# pihat2.net
KiCad netlist of a schematic drawn in EAGLE
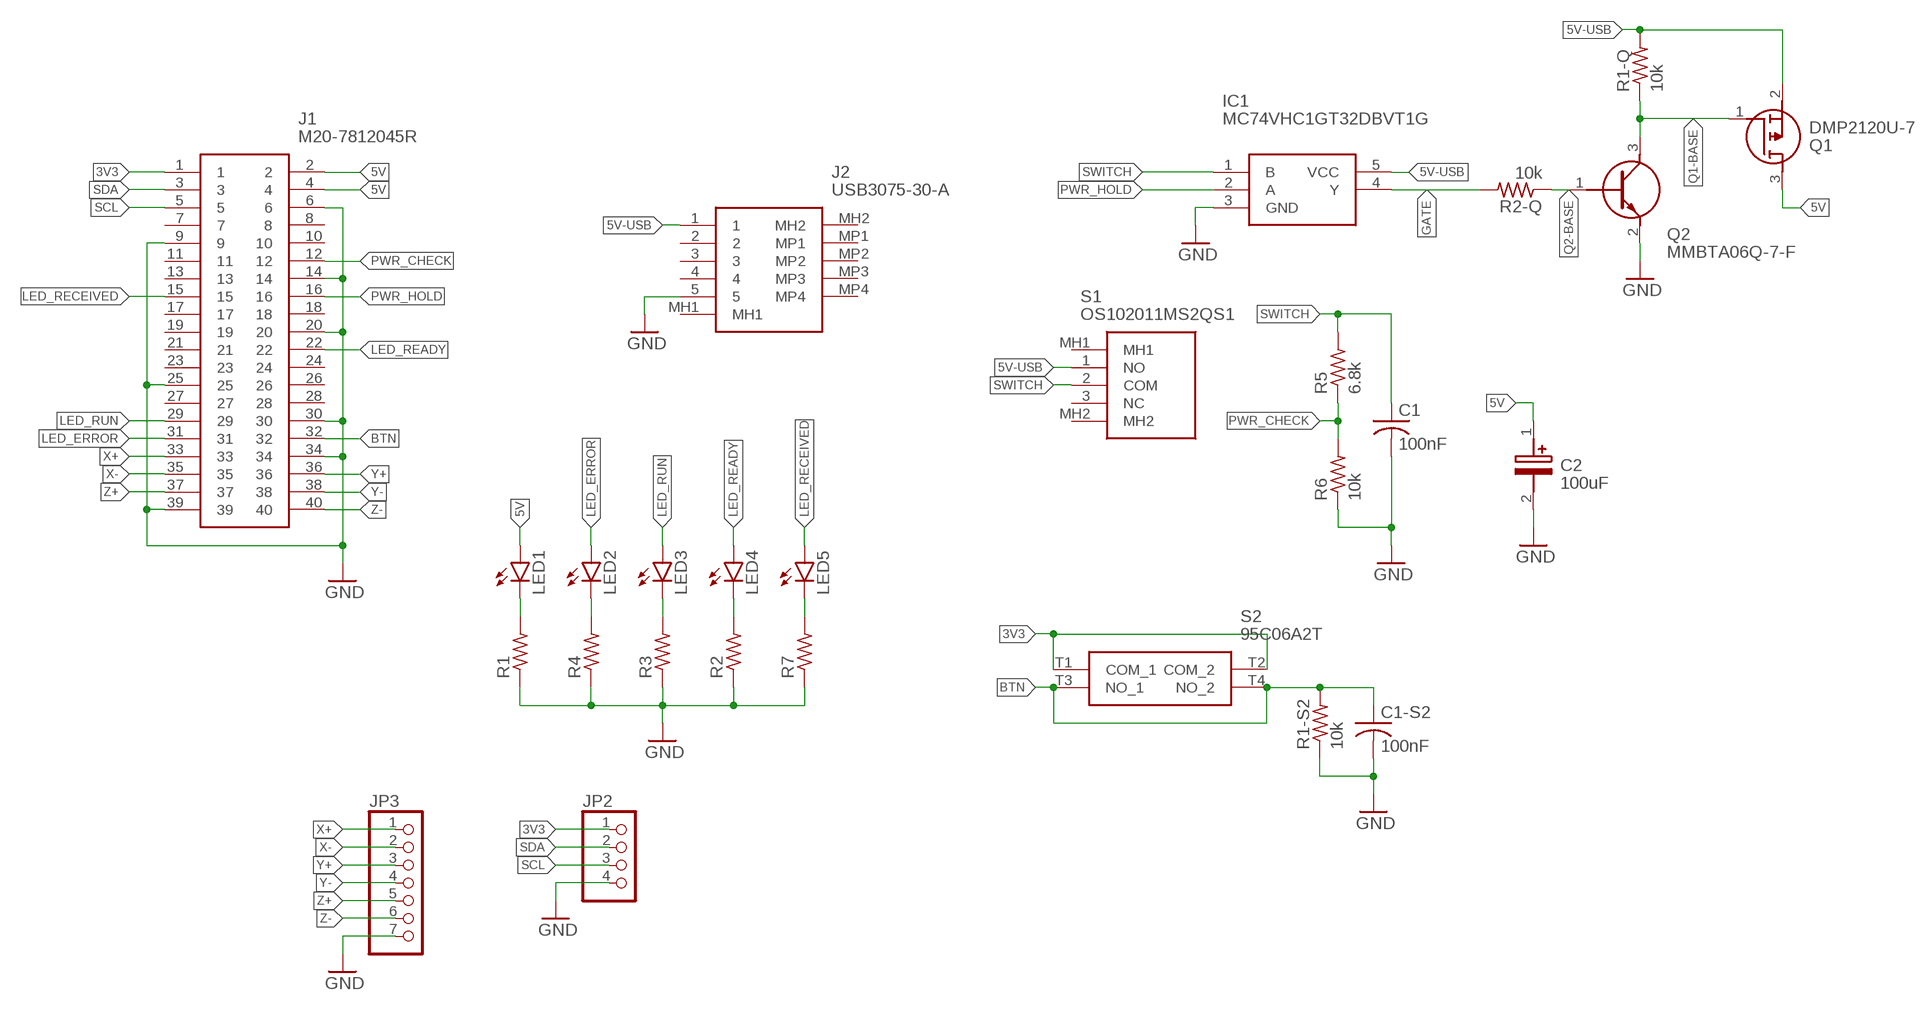
[diagram p0: schematic, sheet 1]

(export (version "E")
  (design (tool "Eeschema 10.0.6"))
  (components
    (comp (ref "C1")
      (value "100nF")
      (footprint "eagle-import:C0805")
      (libsource (lib "eagle-import") (part "C-USC0805"))
    )
    (comp (ref "C1-S2")
      (value "100nF")
      (footprint "eagle-import:C0805")
      (libsource (lib "eagle-import") (part "C-USC0805"))
    )
    (comp (ref "C2")
      (value "100uF")
      (footprint "eagle-import:CAPPRD250W45D630H500")
      (fields
        (field (name "MANUFACTURER_PART_NUMBER") "10ML100MEFC6.3X5")
        (field (name "MOUSER_PART_NUMBER") "232-10ML100MEFC6.3X5")
      )
      (libsource (lib "eagle-import") (part "10ML100MEFC6.3X5"))
    )
    (comp (ref "IC1")
      (value "MC74VHC1GT32DBVT1G")
      (footprint "eagle-import:MC74VHC1GT32DBVT1G")
      (fields (field (name "MOUSER_PART_NUMBER") "863-MC74VHC1GT32DBVG"))
      (libsource (lib "eagle-import") (part "MC74VHC1GT32DBVT1G"))
    )
    (comp (ref "J1")
      (value "M20-7812045R")
      (footprint "eagle-import:M207812045R")
      (fields (field (name "MOUSER_PART_NUMBER") "855-M20-7812045R"))
      (libsource (lib "eagle-import") (part "M20-7812045R"))
    )
    (comp (ref "J2")
      (value "USB3075-30-A")
      (footprint "eagle-import:USB307530A")
      (fields (field (name "MOUSER_PART_NUMBER") "640-USB3075-30-A"))
      (libsource (lib "eagle-import") (part "USB3075-30-A"))
    )
    (comp (ref "JP2")
      (value "PINHD-1X4")
      (footprint "eagle-import:1X04")
      (libsource (lib "eagle-import") (part "PINHD-1X4"))
    )
    (comp (ref "JP3")
      (value "PINHD-1X7")
      (footprint "eagle-import:1X07")
      (libsource (lib "eagle-import") (part "PINHD-1X7"))
    )
    (comp (ref "LED1")
      (value "LED5MM")
      (footprint "eagle-import:LED5MM")
      (libsource (lib "eagle-import") (part "LED5MM"))
    )
    (comp (ref "LED2")
      (value "LED5MM")
      (footprint "eagle-import:LED5MM")
      (libsource (lib "eagle-import") (part "LED5MM"))
    )
    (comp (ref "LED3")
      (value "LED5MM")
      (footprint "eagle-import:LED5MM")
      (libsource (lib "eagle-import") (part "LED5MM"))
    )
    (comp (ref "LED4")
      (value "LED5MM")
      (footprint "eagle-import:LED5MM")
      (libsource (lib "eagle-import") (part "LED5MM"))
    )
    (comp (ref "LED5")
      (value "LED5MM")
      (footprint "eagle-import:LED5MM")
      (libsource (lib "eagle-import") (part "LED5MM"))
    )
    (comp (ref "Q1")
      (value "DMP2120U-7")
      (footprint "eagle-import:SOT96P240X110-3N")
      (fields (field (name "MOUSER_PART_NUMBER") "621-DMP2120U-7"))
      (libsource (lib "eagle-import") (part "DMP2120U-7"))
    )
    (comp (ref "Q2")
      (value "MMBTA06Q-7-F")
      (footprint "eagle-import:SOT95P240X120-3N")
      (fields (field (name "MOUSER_PART_NUMBER") "621-MMBTA06Q-7-F"))
      (libsource (lib "eagle-import") (part "MMBTA06Q-7-F"))
    )
    (comp (ref "R1")
      (value "R-US_R0805")
      (footprint "eagle-import:R0805")
      (libsource (lib "eagle-import") (part "R-US_R0805"))
    )
    (comp (ref "R1-Q")
      (value "10k")
      (footprint "eagle-import:R0805")
      (libsource (lib "eagle-import") (part "R-US_R0805"))
    )
    (comp (ref "R1-S2")
      (value "10k")
      (footprint "eagle-import:R0805")
      (libsource (lib "eagle-import") (part "R-US_R0805"))
    )
    (comp (ref "R2")
      (value "R-US_R0805")
      (footprint "eagle-import:R0805")
      (libsource (lib "eagle-import") (part "R-US_R0805"))
    )
    (comp (ref "R2-Q")
      (value "10k")
      (footprint "eagle-import:R0805")
      (libsource (lib "eagle-import") (part "R-US_R0805"))
    )
    (comp (ref "R3")
      (value "R-US_R0805")
      (footprint "eagle-import:R0805")
      (libsource (lib "eagle-import") (part "R-US_R0805"))
    )
    (comp (ref "R4")
      (value "R-US_R0805")
      (footprint "eagle-import:R0805")
      (libsource (lib "eagle-import") (part "R-US_R0805"))
    )
    (comp (ref "R5")
      (value "6.8k")
      (footprint "eagle-import:R0805")
      (libsource (lib "eagle-import") (part "R-US_R0805"))
    )
    (comp (ref "R6")
      (value "10k")
      (footprint "eagle-import:R0805")
      (libsource (lib "eagle-import") (part "R-US_R0805"))
    )
    (comp (ref "R7")
      (value "R-US_R0805")
      (footprint "eagle-import:R0805")
      (libsource (lib "eagle-import") (part "R-US_R0805"))
    )
    (comp (ref "S1")
      (value "OS102011MS2QS1")
      (footprint "eagle-import:OS102011MS2QS1")
      (fields (field (name "MOUSER_PART_NUMBER") "611-OS102011MS2QS1"))
      (libsource (lib "eagle-import") (part "OS102011MS2QS1"))
    )
    (comp (ref "S2")
      (value "95C06A2T")
      (footprint "eagle-import:95C06A2T")
      (fields (field (name "MOUSER_PART_NUMBER") "706-95C06A2T"))
      (libsource (lib "eagle-import") (part "95C06A2T"))
    )
  )
  (nets
    (net (code "1") (name "3V3") (class "Default")
      (node (ref "J1") (pin "1") (pinfunction "1_1") (pintype "bidirectional"))
      (node (ref "JP2") (pin "1") (pinfunction "1_1") (pintype "passive"))
      (node (ref "S2") (pin "T1") (pinfunction "COM_1_T1") (pintype "bidirectional"))
      (node (ref "S2") (pin "T2") (pinfunction "COM_2_T2") (pintype "bidirectional"))
    )
    (net (code "2") (name "5V") (class "Default")
      (node (ref "C2") (pin "1") (pinfunction "+_1") (pintype "bidirectional"))
      (node (ref "J1") (pin "2") (pinfunction "2_2") (pintype "bidirectional"))
      (node (ref "J1") (pin "4") (pinfunction "4_4") (pintype "bidirectional"))
      (node (ref "LED1") (pin "A") (pinfunction "A_A") (pintype "passive"))
      (node (ref "Q1") (pin "3") (pinfunction "D_3") (pintype "bidirectional"))
    )
    (net (code "3") (name "5V-USB") (class "Default")
      (node (ref "IC1") (pin "5") (pinfunction "VCC_5") (pintype "bidirectional"))
      (node (ref "J2") (pin "1") (pinfunction "1_1") (pintype "bidirectional"))
      (node (ref "Q1") (pin "2") (pinfunction "S_2") (pintype "bidirectional"))
      (node (ref "R1-Q") (pin "2") (pinfunction "2_2") (pintype "passive"))
      (node (ref "S1") (pin "1") (pinfunction "NO_1") (pintype "bidirectional"))
    )
    (net (code "4") (name "BTN") (class "Default")
      (node (ref "C1-S2") (pin "1") (pinfunction "1_1") (pintype "passive"))
      (node (ref "J1") (pin "32") (pinfunction "32_32") (pintype "bidirectional"))
      (node (ref "R1-S2") (pin "2") (pinfunction "2_2") (pintype "passive"))
      (node (ref "S2") (pin "T3") (pinfunction "NO_1_T3") (pintype "bidirectional"))
      (node (ref "S2") (pin "T4") (pinfunction "NO_2_T4") (pintype "bidirectional"))
    )
    (net (code "5") (name "GATE") (class "Default")
      (node (ref "IC1") (pin "4") (pinfunction "Y_4") (pintype "bidirectional"))
      (node (ref "R2-Q") (pin "2") (pinfunction "2_2") (pintype "passive"))
    )
    (net (code "6") (name "GND") (class "Default")
      (node (ref "C1") (pin "2") (pinfunction "2_2") (pintype "passive"))
      (node (ref "C1-S2") (pin "2") (pinfunction "2_2") (pintype "passive"))
      (node (ref "C2") (pin "2") (pinfunction "-_2") (pintype "bidirectional"))
      (node (ref "IC1") (pin "3") (pinfunction "GND_3") (pintype "bidirectional"))
      (node (ref "J1") (pin "14") (pinfunction "14_14") (pintype "bidirectional"))
      (node (ref "J1") (pin "20") (pinfunction "20_20") (pintype "bidirectional"))
      (node (ref "J1") (pin "25") (pinfunction "25_25") (pintype "bidirectional"))
      (node (ref "J1") (pin "30") (pinfunction "30_30") (pintype "bidirectional"))
      (node (ref "J1") (pin "34") (pinfunction "34_34") (pintype "bidirectional"))
      (node (ref "J1") (pin "39") (pinfunction "39_39") (pintype "bidirectional"))
      (node (ref "J1") (pin "6") (pinfunction "6_6") (pintype "bidirectional"))
      (node (ref "J1") (pin "9") (pinfunction "9_9") (pintype "bidirectional"))
      (node (ref "J2") (pin "5") (pinfunction "5_5") (pintype "bidirectional"))
      (node (ref "JP2") (pin "4") (pinfunction "4_4") (pintype "passive"))
      (node (ref "JP3") (pin "7") (pinfunction "7_7") (pintype "passive"))
      (node (ref "Q2") (pin "2") (pinfunction "E_2") (pintype "bidirectional"))
      (node (ref "R1") (pin "1") (pinfunction "1_1") (pintype "passive"))
      (node (ref "R1-S2") (pin "1") (pinfunction "1_1") (pintype "passive"))
      (node (ref "R2") (pin "1") (pinfunction "1_1") (pintype "passive"))
      (node (ref "R3") (pin "1") (pinfunction "1_1") (pintype "passive"))
      (node (ref "R4") (pin "1") (pinfunction "1_1") (pintype "passive"))
      (node (ref "R6") (pin "1") (pinfunction "1_1") (pintype "passive"))
      (node (ref "R7") (pin "1") (pinfunction "1_1") (pintype "passive"))
    )
    (net (code "7") (name "LED_ERROR") (class "Default")
      (node (ref "J1") (pin "31") (pinfunction "31_31") (pintype "bidirectional"))
      (node (ref "LED2") (pin "A") (pinfunction "A_A") (pintype "passive"))
    )
    (net (code "8") (name "LED_READY") (class "Default")
      (node (ref "J1") (pin "22") (pinfunction "22_22") (pintype "bidirectional"))
      (node (ref "LED4") (pin "A") (pinfunction "A_A") (pintype "passive"))
    )
    (net (code "9") (name "LED_RECEIVED") (class "Default")
      (node (ref "J1") (pin "15") (pinfunction "15_15") (pintype "bidirectional"))
      (node (ref "LED5") (pin "A") (pinfunction "A_A") (pintype "passive"))
    )
    (net (code "10") (name "LED_RUN") (class "Default")
      (node (ref "J1") (pin "29") (pinfunction "29_29") (pintype "bidirectional"))
      (node (ref "LED3") (pin "A") (pinfunction "A_A") (pintype "passive"))
    )
    (net (code "11") (name "Net-(LED1-C)") (class "Default")
      (node (ref "LED1") (pin "K") (pinfunction "C_K") (pintype "passive"))
      (node (ref "R1") (pin "2") (pinfunction "2_2") (pintype "passive"))
    )
    (net (code "12") (name "Net-(LED2-C)") (class "Default")
      (node (ref "LED2") (pin "K") (pinfunction "C_K") (pintype "passive"))
      (node (ref "R4") (pin "2") (pinfunction "2_2") (pintype "passive"))
    )
    (net (code "13") (name "Net-(LED3-C)") (class "Default")
      (node (ref "LED3") (pin "K") (pinfunction "C_K") (pintype "passive"))
      (node (ref "R3") (pin "2") (pinfunction "2_2") (pintype "passive"))
    )
    (net (code "14") (name "Net-(LED4-C)") (class "Default")
      (node (ref "LED4") (pin "K") (pinfunction "C_K") (pintype "passive"))
      (node (ref "R2") (pin "2") (pinfunction "2_2") (pintype "passive"))
    )
    (net (code "15") (name "Net-(LED5-C)") (class "Default")
      (node (ref "LED5") (pin "K") (pinfunction "C_K") (pintype "passive"))
      (node (ref "R7") (pin "2") (pinfunction "2_2") (pintype "passive"))
    )
    (net (code "16") (name "PWR_CHECK") (class "Default")
      (node (ref "J1") (pin "12") (pinfunction "12_12") (pintype "bidirectional"))
      (node (ref "R5") (pin "1") (pinfunction "1_1") (pintype "passive"))
      (node (ref "R6") (pin "2") (pinfunction "2_2") (pintype "passive"))
    )
    (net (code "17") (name "PWR_HOLD") (class "Default")
      (node (ref "IC1") (pin "2") (pinfunction "A_2") (pintype "bidirectional"))
      (node (ref "J1") (pin "16") (pinfunction "16_16") (pintype "bidirectional"))
    )
    (net (code "18") (name "Q1-BASE") (class "Default")
      (node (ref "Q1") (pin "1") (pinfunction "G_1") (pintype "bidirectional"))
      (node (ref "Q2") (pin "3") (pinfunction "C_3") (pintype "bidirectional"))
      (node (ref "R1-Q") (pin "1") (pinfunction "1_1") (pintype "passive"))
    )
    (net (code "19") (name "Q2-BASE") (class "Default")
      (node (ref "Q2") (pin "1") (pinfunction "B_1") (pintype "bidirectional"))
      (node (ref "R2-Q") (pin "1") (pinfunction "1_1") (pintype "passive"))
    )
    (net (code "20") (name "SCL") (class "Default")
      (node (ref "J1") (pin "5") (pinfunction "5_5") (pintype "bidirectional"))
      (node (ref "JP2") (pin "3") (pinfunction "3_3") (pintype "passive"))
    )
    (net (code "21") (name "SDA") (class "Default")
      (node (ref "J1") (pin "3") (pinfunction "3_3") (pintype "bidirectional"))
      (node (ref "JP2") (pin "2") (pinfunction "2_2") (pintype "passive"))
    )
    (net (code "22") (name "SWITCH") (class "Default")
      (node (ref "C1") (pin "1") (pinfunction "1_1") (pintype "passive"))
      (node (ref "IC1") (pin "1") (pinfunction "B_1") (pintype "bidirectional"))
      (node (ref "R5") (pin "2") (pinfunction "2_2") (pintype "passive"))
      (node (ref "S1") (pin "2") (pinfunction "COM_2") (pintype "bidirectional"))
    )
    (net (code "23") (name "X+") (class "Default")
      (node (ref "J1") (pin "33") (pinfunction "33_33") (pintype "bidirectional"))
      (node (ref "JP3") (pin "1") (pinfunction "1_1") (pintype "passive"))
    )
    (net (code "24") (name "X-") (class "Default")
      (node (ref "J1") (pin "35") (pinfunction "35_35") (pintype "bidirectional"))
      (node (ref "JP3") (pin "2") (pinfunction "2_2") (pintype "passive"))
    )
    (net (code "25") (name "Y+") (class "Default")
      (node (ref "J1") (pin "36") (pinfunction "36_36") (pintype "bidirectional"))
      (node (ref "JP3") (pin "3") (pinfunction "3_3") (pintype "passive"))
    )
    (net (code "26") (name "Y-") (class "Default")
      (node (ref "J1") (pin "38") (pinfunction "38_38") (pintype "bidirectional"))
      (node (ref "JP3") (pin "4") (pinfunction "4_4") (pintype "passive"))
    )
    (net (code "27") (name "Z+") (class "Default")
      (node (ref "J1") (pin "37") (pinfunction "37_37") (pintype "bidirectional"))
      (node (ref "JP3") (pin "5") (pinfunction "5_5") (pintype "passive"))
    )
    (net (code "28") (name "Z-") (class "Default")
      (node (ref "J1") (pin "40") (pinfunction "40_40") (pintype "bidirectional"))
      (node (ref "JP3") (pin "6") (pinfunction "6_6") (pintype "passive"))
    )
    (net (code "29") (name "unconnected-(J1-Pad7)") (class "Default")
      (node (ref "J1") (pin "7") (pinfunction "7_7") (pintype "bidirectional"))
    )
    (net (code "30") (name "unconnected-(J1-Pad8)") (class "Default")
      (node (ref "J1") (pin "8") (pinfunction "8_8") (pintype "bidirectional"))
    )
    (net (code "31") (name "unconnected-(J1-Pad10)") (class "Default")
      (node (ref "J1") (pin "10") (pinfunction "10_10") (pintype "bidirectional"))
    )
    (net (code "32") (name "unconnected-(J1-Pad11)") (class "Default")
      (node (ref "J1") (pin "11") (pinfunction "11_11") (pintype "bidirectional"))
    )
    (net (code "33") (name "unconnected-(J1-Pad13)") (class "Default")
      (node (ref "J1") (pin "13") (pinfunction "13_13") (pintype "bidirectional"))
    )
    (net (code "34") (name "unconnected-(J1-Pad17)") (class "Default")
      (node (ref "J1") (pin "17") (pinfunction "17_17") (pintype "bidirectional"))
    )
    (net (code "35") (name "unconnected-(J1-Pad18)") (class "Default")
      (node (ref "J1") (pin "18") (pinfunction "18_18") (pintype "bidirectional"))
    )
    (net (code "36") (name "unconnected-(J1-Pad19)") (class "Default")
      (node (ref "J1") (pin "19") (pinfunction "19_19") (pintype "bidirectional"))
    )
    (net (code "37") (name "unconnected-(J1-Pad21)") (class "Default")
      (node (ref "J1") (pin "21") (pinfunction "21_21") (pintype "bidirectional"))
    )
    (net (code "38") (name "unconnected-(J1-Pad23)") (class "Default")
      (node (ref "J1") (pin "23") (pinfunction "23_23") (pintype "bidirectional"))
    )
    (net (code "39") (name "unconnected-(J1-Pad24)") (class "Default")
      (node (ref "J1") (pin "24") (pinfunction "24_24") (pintype "bidirectional"))
    )
    (net (code "40") (name "unconnected-(J1-Pad26)") (class "Default")
      (node (ref "J1") (pin "26") (pinfunction "26_26") (pintype "bidirectional"))
    )
    (net (code "41") (name "unconnected-(J1-Pad27)") (class "Default")
      (node (ref "J1") (pin "27") (pinfunction "27_27") (pintype "bidirectional"))
    )
    (net (code "42") (name "unconnected-(J1-Pad28)") (class "Default")
      (node (ref "J1") (pin "28") (pinfunction "28_28") (pintype "bidirectional"))
    )
    (net (code "43") (name "unconnected-(J2-Pad2)") (class "Default")
      (node (ref "J2") (pin "2") (pinfunction "2_2") (pintype "bidirectional"))
    )
    (net (code "44") (name "unconnected-(J2-Pad3)") (class "Default")
      (node (ref "J2") (pin "3") (pinfunction "3_3") (pintype "bidirectional"))
    )
    (net (code "45") (name "unconnected-(J2-Pad4)") (class "Default")
      (node (ref "J2") (pin "4") (pinfunction "4_4") (pintype "bidirectional"))
    )
    (net (code "46") (name "unconnected-(J2-PadMH1)") (class "Default")
      (node (ref "J2") (pin "MH1") (pinfunction "MH1_MH1") (pintype "bidirectional"))
    )
    (net (code "47") (name "unconnected-(J2-PadMH2)") (class "Default")
      (node (ref "J2") (pin "MH2") (pinfunction "MH2_MH2") (pintype "bidirectional"))
    )
    (net (code "48") (name "unconnected-(J2-PadMP1)") (class "Default")
      (node (ref "J2") (pin "MP1") (pinfunction "MP1_MP1") (pintype "bidirectional"))
    )
    (net (code "49") (name "unconnected-(J2-PadMP2)") (class "Default")
      (node (ref "J2") (pin "MP2") (pinfunction "MP2_MP2") (pintype "bidirectional"))
    )
    (net (code "50") (name "unconnected-(J2-PadMP3)") (class "Default")
      (node (ref "J2") (pin "MP3") (pinfunction "MP3_MP3") (pintype "bidirectional"))
    )
    (net (code "51") (name "unconnected-(J2-PadMP4)") (class "Default")
      (node (ref "J2") (pin "MP4") (pinfunction "MP4_MP4") (pintype "bidirectional"))
    )
    (net (code "52") (name "unconnected-(S1-NC-Pad3)") (class "Default")
      (node (ref "S1") (pin "3") (pinfunction "NC_3") (pintype "no_connect"))
    )
    (net (code "53") (name "unconnected-(S1-PadMH1)") (class "Default")
      (node (ref "S1") (pin "MH1") (pinfunction "MH1_MH1") (pintype "bidirectional"))
    )
    (net (code "54") (name "unconnected-(S1-PadMH2)") (class "Default")
      (node (ref "S1") (pin "MH2") (pinfunction "MH2_MH2") (pintype "bidirectional"))
    )
  )
)
